# Drimp_Quadcopter.net
KiCad netlist of a schematic drawn in Altium Designer
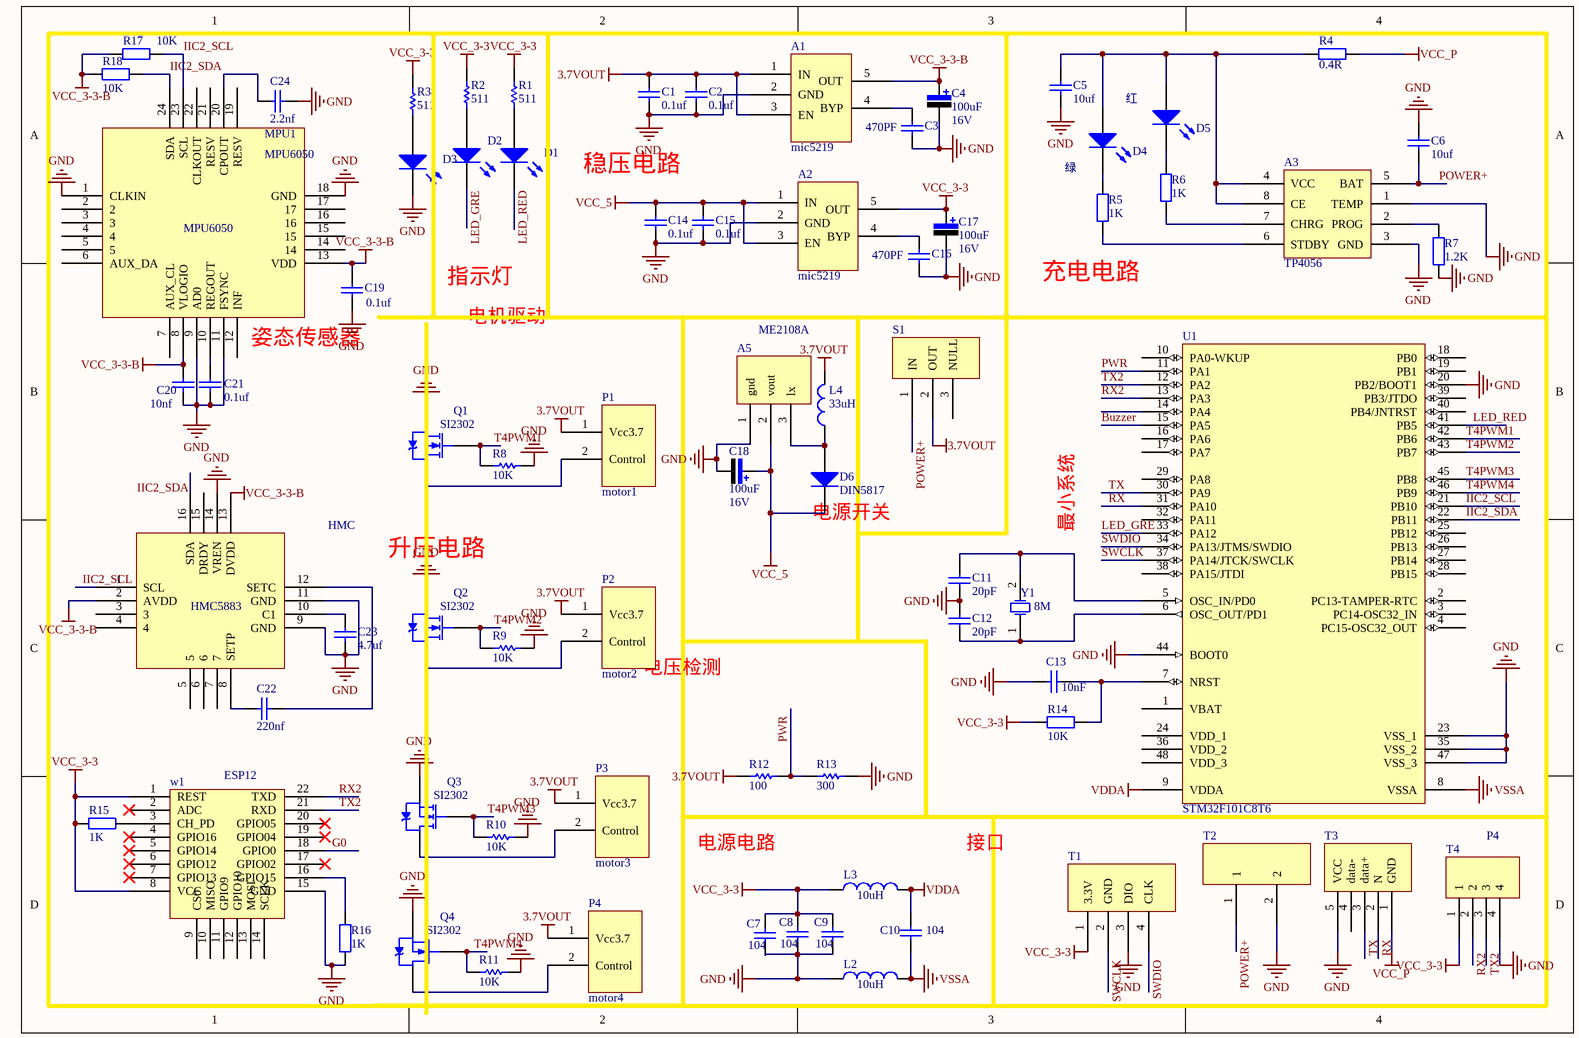
[diagram p0: Drimp_Quadcopter.SchDoc]

(export (version "E")
  (design (tool "Eeschema 10.0.6"))
  (components
    (comp (ref "A1")
      (value "mic5219")
      (footprint "SOT23-5")
      (description "低压差转3.3V")
      (libsource (lib "My") (part "mic5219"))
    )
    (comp (ref "A2")
      (value "mic5219")
      (footprint "SOT23-5")
      (description "低压差转3.3V")
      (libsource (lib "My") (part "mic5219"))
    )
    (comp (ref "A3") (value "TP4056") (footprint "SOP8") (libsource (lib "My") (part "TP4056")))
    (comp (ref "A5") (value "ME2108A") (footprint "SOT-89_M") (libsource (lib "My") (part "bl8530")))
    (comp (ref "C1")
      (value "0.1uf")
      (footprint "C-RAD-0603")
      (description "无极性电容")
      (fields (field (name "Comment") "Cap") (field (name "PUBLISHER") "Altium Limited"))
      (libsource (lib "Fszhang") (part "Cap"))
    )
    (comp (ref "C2")
      (value "0.1uf")
      (footprint "C-RAD-0603")
      (description "无极性电容")
      (fields (field (name "Comment") "Cap") (field (name "PUBLISHER") "Altium Limited"))
      (libsource (lib "Fszhang") (part "Cap"))
    )
    (comp (ref "C3")
      (value "470PF")
      (footprint "C-RAD-0603")
      (description "无极性电容")
      (fields (field (name "Comment") "Cap") (field (name "PUBLISHER") "Altium Limited"))
      (libsource (lib "Fszhang") (part "Cap"))
    )
    (comp (ref "C4")
      (value "100uF")
      (footprint "CAP-6032")
      (description "极性电解电容")
      (fields
        (field (name "VOL") "16V")
        (field (name "Comment") "Cap Pol")
        (field (name "PUBLISHER") "Altium Limited")
      )
      (libsource (lib "Fszhang") (part "Cap Pol"))
    )
    (comp (ref "C5")
      (value "10uf")
      (footprint "C-RAD-0603")
      (description "无极性电容")
      (fields (field (name "Comment") "Cap") (field (name "PUBLISHER") "Altium Limited"))
      (libsource (lib "Fszhang") (part "Cap"))
    )
    (comp (ref "C6")
      (value "10uf")
      (footprint "C-RAD-0603")
      (description "无极性电容")
      (fields (field (name "Comment") "Cap") (field (name "PUBLISHER") "Altium Limited"))
      (libsource (lib "Fszhang") (part "Cap"))
    )
    (comp (ref "C7")
      (value "104")
      (footprint "0603-N-CAP")
      (description "Capacitor")
      (fields (field (name "Comment") "Cap") (field (name "PUBLISHER") "Altium Limited"))
      (libsource (lib "Miscellaneous Devices") (part "Cap"))
    )
    (comp (ref "C8")
      (value "104")
      (footprint "0603-N-CAP")
      (description "Capacitor")
      (fields (field (name "Comment") "Cap") (field (name "PUBLISHER") "Altium Limited"))
      (libsource (lib "Miscellaneous Devices") (part "Cap"))
    )
    (comp (ref "C9")
      (value "104")
      (footprint "0603-N-CAP")
      (description "Capacitor")
      (fields (field (name "Comment") "Cap") (field (name "PUBLISHER") "Altium Limited"))
      (libsource (lib "Miscellaneous Devices") (part "Cap"))
    )
    (comp (ref "C10")
      (value "104")
      (footprint "0603-N-CAP")
      (description "Capacitor")
      (fields (field (name "Comment") "Cap") (field (name "PUBLISHER") "Altium Limited"))
      (libsource (lib "Miscellaneous Devices") (part "Cap"))
    )
    (comp (ref "C11")
      (value "20pF")
      (footprint "0603-N-CAP")
      (description "Capacitor")
      (fields (field (name "Comment") "Cap") (field (name "PUBLISHER") "Altium Limited"))
      (libsource (lib "Miscellaneous Devices") (part "Cap"))
    )
    (comp (ref "C12")
      (value "20pF")
      (footprint "0603-N-CAP")
      (description "Capacitor")
      (fields (field (name "Comment") "Cap") (field (name "PUBLISHER") "Altium Limited"))
      (libsource (lib "Miscellaneous Devices") (part "Cap"))
    )
    (comp (ref "C13")
      (value "10nF")
      (footprint "0603-N-CAP")
      (description "Capacitor")
      (fields (field (name "Comment") "Cap") (field (name "PUBLISHER") "Altium Limited"))
      (libsource (lib "Miscellaneous Devices") (part "Cap"))
    )
    (comp (ref "C14")
      (value "0.1uf")
      (footprint "C-RAD-0603")
      (description "无极性电容")
      (fields (field (name "Comment") "Cap") (field (name "PUBLISHER") "Altium Limited"))
      (libsource (lib "Fszhang") (part "Cap"))
    )
    (comp (ref "C15")
      (value "0.1uf")
      (footprint "C-RAD-0603")
      (description "无极性电容")
      (fields (field (name "Comment") "Cap") (field (name "PUBLISHER") "Altium Limited"))
      (libsource (lib "Fszhang") (part "Cap"))
    )
    (comp (ref "C16")
      (value "470PF")
      (footprint "C-RAD-0603")
      (description "无极性电容")
      (fields (field (name "Comment") "Cap") (field (name "PUBLISHER") "Altium Limited"))
      (libsource (lib "Fszhang") (part "Cap"))
    )
    (comp (ref "C17")
      (value "100uF")
      (footprint "CAP-6032")
      (description "极性电解电容")
      (fields
        (field (name "VOL") "16V")
        (field (name "Comment") "Cap Pol")
        (field (name "PUBLISHER") "Altium Limited")
      )
      (libsource (lib "Fszhang") (part "Cap Pol"))
    )
    (comp (ref "C18")
      (value "100uF")
      (footprint "CAP-6032")
      (description "极性电解电容")
      (fields
        (field (name "VOL") "16V")
        (field (name "Comment") "Cap Pol")
        (field (name "PUBLISHER") "Altium Limited")
      )
      (libsource (lib "") (part "Cap Pol_1"))
    )
    (comp (ref "C19")
      (value "0.1uf")
      (footprint "C-RAD-0603")
      (description "无极性电容")
      (fields (field (name "Comment") "Cap") (field (name "PUBLISHER") "Altium Limited"))
      (libsource (lib "Fszhang") (part "Cap"))
    )
    (comp (ref "C20")
      (value "10nf")
      (footprint "C-RAD-0603")
      (description "无极性电容")
      (fields (field (name "Comment") "Cap") (field (name "PUBLISHER") "Altium Limited"))
      (libsource (lib "Fszhang") (part "Cap"))
    )
    (comp (ref "C21")
      (value "0.1uf")
      (footprint "C-RAD-0603")
      (description "无极性电容")
      (fields (field (name "Comment") "Cap") (field (name "PUBLISHER") "Altium Limited"))
      (libsource (lib "Fszhang") (part "Cap"))
    )
    (comp (ref "C22")
      (value "220nf")
      (footprint "C-RAD-0603")
      (description "无极性电容")
      (fields (field (name "Comment") "Cap") (field (name "PUBLISHER") "Altium Limited"))
      (libsource (lib "Fszhang") (part "Cap"))
    )
    (comp (ref "C23")
      (value "4.7uf")
      (footprint "C-RAD-0603")
      (description "无极性电容")
      (fields (field (name "Comment") "Cap") (field (name "PUBLISHER") "Altium Limited"))
      (libsource (lib "Fszhang") (part "Cap"))
    )
    (comp (ref "C24")
      (value "2.2nf")
      (footprint "C-RAD-0603")
      (description "无极性电容")
      (fields (field (name "Comment") "Cap") (field (name "PUBLISHER") "Altium Limited"))
      (libsource (lib "Fszhang") (part "Cap"))
    )
    (comp (ref "D1")
      (value "D2")
      (footprint "6-0805_N")
      (description "Typical BLUE SiC LED")
      (fields (field (name "PUBLISHER") "Altium Limited"))
      (libsource (lib "Miscellaneous Devices") (part "LED3"))
    )
    (comp (ref "D2")
      (value "D2")
      (footprint "6-0805_N")
      (description "Typical BLUE SiC LED")
      (fields (field (name "PUBLISHER") "Altium Limited"))
      (libsource (lib "Miscellaneous Devices") (part "LED3"))
    )
    (comp (ref "D3")
      (value "D2")
      (footprint "6-0805_N")
      (description "Typical BLUE SiC LED")
      (fields (field (name "PUBLISHER") "Altium Limited"))
      (libsource (lib "Miscellaneous Devices") (part "LED3"))
    )
    (comp (ref "D4")
      (value "LED0")
      (footprint "LED0805G")
      (description "发光二极管")
      (fields (field (name "PUBLISHER") "Altium Limited"))
      (libsource (lib "Fszhang") (part "LED0"))
    )
    (comp (ref "D5")
      (value "LED0")
      (footprint "LED0805R")
      (description "发光二极管")
      (fields (field (name "PUBLISHER") "Altium Limited"))
      (libsource (lib "Fszhang") (part "LED0"))
    )
    (comp (ref "D6")
      (value "Diode")
      (footprint "DIODE-SMA")
      (description "二极管")
      (fields (field (name "TYPE") "DIN5817") (field (name "PUBLISHER") "Altium Limited"))
      (libsource (lib "Fszhang") (part "Diode"))
    )
    (comp (ref "HMC")
      (value "Component_1")
      (footprint "HMC5883")
      (libsource (lib "HMC5883") (part "Component_1"))
    )
    (comp (ref "L2")
      (value "10uH")
      (footprint "0603-N - res")
      (description "Inductor")
      (fields (field (name "PUBLISHER") "Altium Limited"))
      (libsource (lib "Miscellaneous Devices") (part "Inductor"))
    )
    (comp (ref "L3")
      (value "10uH")
      (footprint "0603-N - res")
      (description "Inductor")
      (fields (field (name "PUBLISHER") "Altium Limited"))
      (libsource (lib "Miscellaneous Devices") (part "Inductor"))
    )
    (comp (ref "L4")
      (value "33uH")
      (footprint "CD54NP")
      (description "电感")
      (fields (field (name "Comment") "Inductor") (field (name "PUBLISHER") "Altium Limited"))
      (libsource (lib "Fszhang") (part "Inductor"))
    )
    (comp (ref "MPU1") (value "MPU6050") (footprint "MPU6050") (libsource (lib "MPU6050") (part "MPU6050")))
    (comp (ref "P1")
      (value "motor1")
      (footprint "P2-T-1.25")
      (description "电机连接口")
      (libsource (lib "Schlib1") (part "motor"))
    )
    (comp (ref "P2")
      (value "motor2")
      (footprint "P2-T-1.25")
      (description "电机连接口")
      (libsource (lib "Schlib1") (part "motor"))
    )
    (comp (ref "P3")
      (value "motor3")
      (footprint "P2-T-1.25")
      (description "电机连接口")
      (libsource (lib "Schlib1") (part "motor"))
    )
    (comp (ref "P4")
      (value "motor4")
      (footprint "P2-T-1.25")
      (description "电机连接口")
      (libsource (lib "Schlib1") (part "motor"))
    )
    (comp (ref "Q1")
      (value "SI2302")
      (footprint "SOT-23_M")
      (description "HEXFET Power MOSFET")
      (fields (field (name "PUBLISHER") "Altium Limited"))
      (libsource (lib "IR Discrete MOSFET - Power") (part "IRLML2402"))
    )
    (comp (ref "Q2")
      (value "SI2302")
      (footprint "SOT-23_M")
      (description "HEXFET Power MOSFET")
      (fields (field (name "PUBLISHER") "Altium Limited"))
      (libsource (lib "IR Discrete MOSFET - Power") (part "IRLML2402"))
    )
    (comp (ref "Q3")
      (value "SI2302")
      (footprint "SOT-23_M")
      (description "HEXFET Power MOSFET")
      (fields (field (name "PUBLISHER") "Altium Limited"))
      (libsource (lib "IR Discrete MOSFET - Power") (part "IRLML2402"))
    )
    (comp (ref "Q4")
      (value "SI2302")
      (footprint "SOT-23_M")
      (description "HEXFET Power MOSFET")
      (fields (field (name "PUBLISHER") "Altium Limited"))
      (libsource (lib "IR Discrete MOSFET - Power") (part "IRLML2402"))
    )
    (comp (ref "R1")
      (value "511")
      (footprint "0603-N - res")
      (description "Resistor")
      (fields (field (name "Comment") "Res1") (field (name "PUBLISHER") "Altium Limited"))
      (libsource (lib "Miscellaneous Devices") (part "Res1"))
    )
    (comp (ref "R2")
      (value "511")
      (footprint "0603-N - res")
      (description "Resistor")
      (fields (field (name "Comment") "Res1") (field (name "PUBLISHER") "Altium Limited"))
      (libsource (lib "Miscellaneous Devices") (part "Res1"))
    )
    (comp (ref "R3")
      (value "511")
      (footprint "0603-N - res")
      (description "Resistor")
      (fields (field (name "Comment") "Res1") (field (name "PUBLISHER") "Altium Limited"))
      (libsource (lib "Miscellaneous Devices") (part "Res1"))
    )
    (comp (ref "R4")
      (value "0.4R")
      (footprint "1206")
      (description "贴片电阻")
      (fields (field (name "Comment") "Res1") (field (name "PUBLISHER") "Altium Limited"))
      (libsource (lib "") (part "Res1_1"))
    )
    (comp (ref "R5")
      (value "1K")
      (footprint "0603-1")
      (description "贴片电阻")
      (fields (field (name "Comment") "Res1") (field (name "PUBLISHER") "Altium Limited"))
      (libsource (lib "Fszhang") (part "Res1"))
    )
    (comp (ref "R6")
      (value "1K")
      (footprint "0603-1")
      (description "贴片电阻")
      (fields (field (name "Comment") "Res1") (field (name "PUBLISHER") "Altium Limited"))
      (libsource (lib "Fszhang") (part "Res1"))
    )
    (comp (ref "R7")
      (value "1.2K")
      (footprint "0603-1")
      (description "贴片电阻")
      (fields (field (name "Comment") "Res1") (field (name "PUBLISHER") "Altium Limited"))
      (libsource (lib "Fszhang") (part "Res1"))
    )
    (comp (ref "R8")
      (value "10K")
      (footprint "0603-N - res")
      (description "Resistor")
      (fields (field (name "Comment") "Res1") (field (name "PUBLISHER") "Altium Limited"))
      (libsource (lib "Miscellaneous Devices") (part "Res1"))
    )
    (comp (ref "R9")
      (value "10K")
      (footprint "0603-N - res")
      (description "Resistor")
      (fields (field (name "Comment") "Res1") (field (name "PUBLISHER") "Altium Limited"))
      (libsource (lib "Miscellaneous Devices") (part "Res1"))
    )
    (comp (ref "R10")
      (value "10K")
      (footprint "0603-N - res")
      (description "Resistor")
      (fields (field (name "Comment") "Res1") (field (name "PUBLISHER") "Altium Limited"))
      (libsource (lib "Miscellaneous Devices") (part "Res1"))
    )
    (comp (ref "R11")
      (value "10K")
      (footprint "0603-N - res")
      (description "Resistor")
      (fields (field (name "Comment") "Res1") (field (name "PUBLISHER") "Altium Limited"))
      (libsource (lib "Miscellaneous Devices") (part "Res1"))
    )
    (comp (ref "R12")
      (value "100")
      (footprint "0603-N - res")
      (description "Resistor")
      (fields (field (name "Comment") "Res1") (field (name "PUBLISHER") "Altium Limited"))
      (libsource (lib "Miscellaneous Devices") (part "Res1"))
    )
    (comp (ref "R13")
      (value "300")
      (footprint "0603-N - res")
      (description "Resistor")
      (fields (field (name "Comment") "Res1") (field (name "PUBLISHER") "Altium Limited"))
      (libsource (lib "Miscellaneous Devices") (part "Res1"))
    )
    (comp (ref "R14")
      (value "10K")
      (footprint "0603-N - res")
      (description "Resistor")
      (fields (field (name "Comment") "Res2") (field (name "PUBLISHER") "Altium Limited"))
      (libsource (lib "Miscellaneous Devices") (part "Res2"))
    )
    (comp (ref "R15")
      (value "1K")
      (footprint "0603-N - res")
      (description "Resistor")
      (fields (field (name "Comment") "Res2") (field (name "PUBLISHER") "Altium Limited"))
      (libsource (lib "Miscellaneous Devices") (part "Res2"))
    )
    (comp (ref "R16")
      (value "1K")
      (footprint "0603-N - res")
      (description "Resistor")
      (fields (field (name "Comment") "Res2") (field (name "PUBLISHER") "Altium Limited"))
      (libsource (lib "") (part "Res2_1"))
    )
    (comp (ref "R17")
      (value "10K")
      (footprint "0603-N - res")
      (description "Resistor")
      (fields (field (name "Comment") "Res2") (field (name "PUBLISHER") "Altium Limited"))
      (libsource (lib "Miscellaneous Devices") (part "Res2"))
    )
    (comp (ref "R18")
      (value "10K")
      (footprint "0603-N - res")
      (description "Resistor")
      (fields (field (name "Comment") "Res2") (field (name "PUBLISHER") "Altium Limited"))
      (libsource (lib "Miscellaneous Devices") (part "Res2"))
    )
    (comp (ref "S1") (value "switch") (footprint "拨动开关") (libsource (lib "Schlib1") (part "switch")))
    (comp (ref "T1")
      (value "SW_download")
      (footprint "P4_1.25")
      (libsource (lib "Schlib1") (part "SW_download"))
    )
    (comp (ref "T2") (value "P2") (footprint "P2") (libsource (lib "My") (part "P2")))
    (comp (ref "T3") (value "mini usb") (footprint "USB_MICRO_5S_B") (libsource (lib "My") (part "mini usb")))
    (comp (ref "T4") (value "P4") (footprint "P4_1.25") (libsource (lib "My") (part "P4")))
    (comp (ref "U1")
      (value "STM32F101C8T6")
      (footprint "LQFP48_N")
      (description "STM32 ARM-based 32-bit MCU with 64 Kbytes Flash, 48-pin LQFP, Industrial Temperature")
      (fields (field (name "PUBLISHER") "Altium Limited"))
      (libsource (lib "ST Microcontroller 32-Bit STM32") (part "STM32F101C8T6"))
    )
    (comp (ref "w1") (value "ESP12") (footprint "ESP_12_F") (libsource (lib "My") (part "ESP12")))
    (comp (ref "Y1")
      (value "8M")
      (footprint "5032_")
      (description "Crystal Oscillator")
      (fields (field (name "PUBLISHER") "Altium Limited"))
      (libsource (lib "Miscellaneous Devices") (part "XTAL"))
    )
  )
  (nets
    (net (code "1") (name "/Buzzer") (class "Default")
      (node (ref "U1") (pin "15") (pinfunction "PA5_15") (pintype "bidirectional"))
    )
    (net (code "2") (name "/G0") (class "Default")
      (node (ref "w1") (pin "18") (pinfunction "GPIO0_18") (pintype "passive"))
    )
    (net (code "3") (name "/IIC2_SCL") (class "Default")
      (node (ref "HMC") (pin "1") (pinfunction "SCL_1") (pintype "passive"))
      (node (ref "MPU1") (pin "23") (pinfunction "SCL_23") (pintype "passive"))
      (node (ref "R17") (pin "2") (pinfunction "2_2") (pintype "passive"))
      (node (ref "U1") (pin "21") (pinfunction "PB10_21") (pintype "bidirectional"))
    )
    (net (code "4") (name "/IIC2_SDA") (class "Default")
      (node (ref "HMC") (pin "16") (pinfunction "SDA_16") (pintype "passive"))
      (node (ref "MPU1") (pin "24") (pinfunction "SDA_24") (pintype "passive"))
      (node (ref "R18") (pin "2") (pinfunction "2_2") (pintype "passive"))
      (node (ref "U1") (pin "22") (pinfunction "PB11_22") (pintype "bidirectional"))
    )
    (net (code "5") (name "/LED_GRE") (class "Default")
      (node (ref "D2") (pin "2") (pinfunction "K_2") (pintype "passive"))
      (node (ref "U1") (pin "33") (pinfunction "PA12_33") (pintype "bidirectional"))
    )
    (net (code "6") (name "/LED_RED") (class "Default")
      (node (ref "D1") (pin "2") (pinfunction "K_2") (pintype "passive"))
      (node (ref "U1") (pin "41") (pinfunction "PB5_41") (pintype "bidirectional"))
    )
    (net (code "7") (name "/POWER+") (class "Default")
      (node (ref "A3") (pin "5") (pinfunction "BAT_5") (pintype "passive"))
      (node (ref "C6") (pin "1") (pinfunction "1_1") (pintype "passive"))
      (node (ref "S1") (pin "1") (pinfunction "IN_1") (pintype "passive"))
      (node (ref "T2") (pin "1") (pinfunction "1_1") (pintype "passive"))
    )
    (net (code "8") (name "/PWR") (class "Default")
      (node (ref "R12") (pin "2") (pinfunction "2_2") (pintype "passive"))
      (node (ref "R13") (pin "1") (pinfunction "1_1") (pintype "passive"))
      (node (ref "U1") (pin "11") (pinfunction "PA1_11") (pintype "bidirectional"))
    )
    (net (code "9") (name "/RX") (class "Default")
      (node (ref "T3") (pin "2") (pinfunction "N_2") (pintype "passive"))
      (node (ref "U1") (pin "31") (pinfunction "PA10_31") (pintype "bidirectional"))
    )
    (net (code "10") (name "/RX2") (class "Default")
      (node (ref "T4") (pin "2") (pinfunction "2_2") (pintype "passive"))
      (node (ref "U1") (pin "13") (pinfunction "PA3_13") (pintype "bidirectional"))
      (node (ref "w1") (pin "22") (pinfunction "TXD_22") (pintype "passive"))
    )
    (net (code "11") (name "/SWCLK") (class "Default")
      (node (ref "T1") (pin "2") (pinfunction "GND_2") (pintype "passive"))
      (node (ref "U1") (pin "37") (pinfunction "PA14/JTCK/SWCLK_37") (pintype "bidirectional"))
    )
    (net (code "12") (name "/SWDIO") (class "Default")
      (node (ref "T1") (pin "4") (pinfunction "CLK_4") (pintype "passive"))
      (node (ref "U1") (pin "34") (pinfunction "PA13/JTMS/SWDIO_34") (pintype "bidirectional"))
    )
    (net (code "13") (name "/T4PWM1") (class "Default")
      (node (ref "Q1") (pin "1") (pinfunction "G_1") (pintype "passive"))
      (node (ref "R8") (pin "1") (pinfunction "1_1") (pintype "passive"))
      (node (ref "U1") (pin "42") (pinfunction "PB6_42") (pintype "bidirectional"))
    )
    (net (code "14") (name "/T4PWM2") (class "Default")
      (node (ref "Q2") (pin "1") (pinfunction "G_1") (pintype "passive"))
      (node (ref "R9") (pin "1") (pinfunction "1_1") (pintype "passive"))
      (node (ref "U1") (pin "43") (pinfunction "PB7_43") (pintype "bidirectional"))
    )
    (net (code "15") (name "/T4PWM3") (class "Default")
      (node (ref "Q3") (pin "1") (pinfunction "G_1") (pintype "passive"))
      (node (ref "R10") (pin "1") (pinfunction "1_1") (pintype "passive"))
      (node (ref "U1") (pin "45") (pinfunction "PB8_45") (pintype "bidirectional"))
    )
    (net (code "16") (name "/T4PWM4") (class "Default")
      (node (ref "Q4") (pin "1") (pinfunction "G_1") (pintype "passive"))
      (node (ref "R11") (pin "1") (pinfunction "1_1") (pintype "passive"))
      (node (ref "U1") (pin "46") (pinfunction "PB9_46") (pintype "bidirectional"))
    )
    (net (code "17") (name "/TX") (class "Default")
      (node (ref "T3") (pin "3") (pinfunction "data+_3") (pintype "passive"))
      (node (ref "U1") (pin "30") (pinfunction "PA9_30") (pintype "bidirectional"))
    )
    (net (code "18") (name "/TX2") (class "Default")
      (node (ref "T4") (pin "3") (pinfunction "3_3") (pintype "passive"))
      (node (ref "U1") (pin "12") (pinfunction "PA2_12") (pintype "bidirectional"))
      (node (ref "w1") (pin "21") (pinfunction "RXD_21") (pintype "passive"))
    )
    (net (code "19") (name "3.7VOUT") (class "Default")
      (node (ref "A1") (pin "1") (pinfunction "IN_1") (pintype "passive"))
      (node (ref "A1") (pin "3") (pinfunction "EN_3") (pintype "passive"))
      (node (ref "C1") (pin "2") (pinfunction "2_2") (pintype "passive"))
      (node (ref "C2") (pin "2") (pinfunction "2_2") (pintype "passive"))
      (node (ref "L4") (pin "2") (pinfunction "2_2") (pintype "passive"))
      (node (ref "P1") (pin "1") (pinfunction "Vcc3.7_1") (pintype "passive"))
      (node (ref "P2") (pin "1") (pinfunction "Vcc3.7_1") (pintype "passive"))
      (node (ref "P3") (pin "1") (pinfunction "Vcc3.7_1") (pintype "passive"))
      (node (ref "P4") (pin "1") (pinfunction "Vcc3.7_1") (pintype "passive"))
      (node (ref "R12") (pin "1") (pinfunction "1_1") (pintype "passive"))
      (node (ref "S1") (pin "2") (pinfunction "OUT_2") (pintype "passive"))
    )
    (net (code "20") (name "GND") (class "Default")
      (node (ref "A1") (pin "2") (pinfunction "GND_2") (pintype "passive"))
      (node (ref "A2") (pin "2") (pinfunction "GND_2") (pintype "passive"))
      (node (ref "A3") (pin "1") (pinfunction "TEMP_1") (pintype "passive"))
      (node (ref "A3") (pin "3") (pinfunction "GND_3") (pintype "passive"))
      (node (ref "A5") (pin "1") (pinfunction "gnd_1") (pintype "passive"))
      (node (ref "C1") (pin "1") (pinfunction "1_1") (pintype "passive"))
      (node (ref "C11") (pin "1") (pinfunction "1_1") (pintype "passive"))
      (node (ref "C12") (pin "2") (pinfunction "2_2") (pintype "passive"))
      (node (ref "C13") (pin "1") (pinfunction "1_1") (pintype "passive"))
      (node (ref "C14") (pin "1") (pinfunction "1_1") (pintype "passive"))
      (node (ref "C15") (pin "1") (pinfunction "1_1") (pintype "passive"))
      (node (ref "C16") (pin "1") (pinfunction "1_1") (pintype "passive"))
      (node (ref "C17") (pin "2") (pinfunction "2_2") (pintype "passive"))
      (node (ref "C18") (pin "2") (pinfunction "2_2") (pintype "passive"))
      (node (ref "C19") (pin "1") (pinfunction "1_1") (pintype "passive"))
      (node (ref "C2") (pin "1") (pinfunction "1_1") (pintype "passive"))
      (node (ref "C20") (pin "1") (pinfunction "1_1") (pintype "passive"))
      (node (ref "C21") (pin "1") (pinfunction "1_1") (pintype "passive"))
      (node (ref "C23") (pin "1") (pinfunction "1_1") (pintype "passive"))
      (node (ref "C24") (pin "1") (pinfunction "1_1") (pintype "passive"))
      (node (ref "C3") (pin "1") (pinfunction "1_1") (pintype "passive"))
      (node (ref "C4") (pin "2") (pinfunction "2_2") (pintype "passive"))
      (node (ref "C5") (pin "1") (pinfunction "1_1") (pintype "passive"))
      (node (ref "C6") (pin "2") (pinfunction "2_2") (pintype "passive"))
      (node (ref "C7") (pin "1") (pinfunction "1_1") (pintype "passive"))
      (node (ref "C8") (pin "1") (pinfunction "1_1") (pintype "passive"))
      (node (ref "C9") (pin "1") (pinfunction "1_1") (pintype "passive"))
      (node (ref "D3") (pin "2") (pinfunction "K_2") (pintype "passive"))
      (node (ref "HMC") (pin "11") (pinfunction "GND_11") (pintype "passive"))
      (node (ref "HMC") (pin "14") (pinfunction "VREN_14") (pintype "passive"))
      (node (ref "HMC") (pin "9") (pinfunction "GND_9") (pintype "passive"))
      (node (ref "L2") (pin "1") (pinfunction "1_1") (pintype "passive"))
      (node (ref "MPU1") (pin "1") (pinfunction "CLKIN_1") (pintype "passive"))
      (node (ref "MPU1") (pin "11") (pinfunction "FSYNC_11") (pintype "passive"))
      (node (ref "MPU1") (pin "18") (pinfunction "GND_18") (pintype "passive"))
      (node (ref "MPU1") (pin "9") (pinfunction "AD0_9") (pintype "passive"))
      (node (ref "Q1") (pin "2") (pinfunction "S_2") (pintype "passive"))
      (node (ref "Q2") (pin "2") (pinfunction "S_2") (pintype "passive"))
      (node (ref "Q3") (pin "2") (pinfunction "S_2") (pintype "passive"))
      (node (ref "Q4") (pin "2") (pinfunction "S_2") (pintype "passive"))
      (node (ref "R10") (pin "2") (pinfunction "2_2") (pintype "passive"))
      (node (ref "R11") (pin "2") (pinfunction "2_2") (pintype "passive"))
      (node (ref "R13") (pin "2") (pinfunction "2_2") (pintype "passive"))
      (node (ref "R16") (pin "1") (pinfunction "1_1") (pintype "passive"))
      (node (ref "R7") (pin "2") (pinfunction "2_2") (pintype "passive"))
      (node (ref "R8") (pin "2") (pinfunction "2_2") (pintype "passive"))
      (node (ref "R9") (pin "2") (pinfunction "2_2") (pintype "passive"))
      (node (ref "T1") (pin "3") (pinfunction "DIO_3") (pintype "passive"))
      (node (ref "T2") (pin "2") (pinfunction "2_2") (pintype "passive"))
      (node (ref "T3") (pin "5") (pinfunction "VCC_5") (pintype "passive"))
      (node (ref "T4") (pin "4") (pinfunction "4_4") (pintype "passive"))
      (node (ref "U1") (pin "20") (pinfunction "PB2/BOOT1_20") (pintype "bidirectional"))
      (node (ref "U1") (pin "23") (pinfunction "VSS_1_23") (pintype "power_in"))
      (node (ref "U1") (pin "35") (pinfunction "VSS_2_35") (pintype "power_in"))
      (node (ref "U1") (pin "44") (pinfunction "BOOT0_44") (pintype "input"))
      (node (ref "U1") (pin "47") (pinfunction "VSS_3_47") (pintype "power_in"))
      (node (ref "w1") (pin "15") (pinfunction "GND_15") (pintype "passive"))
    )
    (net (code "21") (name "Net-(A1-BYP)") (class "Default")
      (node (ref "A1") (pin "4") (pinfunction "BYP_4") (pintype "passive"))
      (node (ref "C3") (pin "2") (pinfunction "2_2") (pintype "passive"))
    )
    (net (code "22") (name "Net-(A2-BYP)") (class "Default")
      (node (ref "A2") (pin "4") (pinfunction "BYP_4") (pintype "passive"))
      (node (ref "C16") (pin "2") (pinfunction "2_2") (pintype "passive"))
    )
    (net (code "23") (name "Net-(A3-CE)") (class "Default")
      (node (ref "A3") (pin "4") (pinfunction "VCC_4") (pintype "passive"))
      (node (ref "A3") (pin "8") (pinfunction "CE_8") (pintype "passive"))
      (node (ref "C5") (pin "2") (pinfunction "2_2") (pintype "passive"))
      (node (ref "D4") (pin "1") (pinfunction "A_1") (pintype "passive"))
      (node (ref "D5") (pin "1") (pinfunction "A_1") (pintype "passive"))
      (node (ref "R4") (pin "1") (pinfunction "1_1") (pintype "passive"))
    )
    (net (code "24") (name "Net-(A3-CHRG)") (class "Default")
      (node (ref "A3") (pin "7") (pinfunction "CHRG_7") (pintype "passive"))
      (node (ref "R6") (pin "2") (pinfunction "2_2") (pintype "passive"))
    )
    (net (code "25") (name "Net-(A3-PROG)") (class "Default")
      (node (ref "A3") (pin "2") (pinfunction "PROG_2") (pintype "passive"))
      (node (ref "R7") (pin "1") (pinfunction "1_1") (pintype "passive"))
    )
    (net (code "26") (name "Net-(A3-STDBY)") (class "Default")
      (node (ref "A3") (pin "6") (pinfunction "STDBY_6") (pintype "passive"))
      (node (ref "R5") (pin "2") (pinfunction "2_2") (pintype "passive"))
    )
    (net (code "27") (name "Net-(A5-lx)") (class "Default")
      (node (ref "A5") (pin "3") (pinfunction "lx_3") (pintype "passive"))
      (node (ref "D6") (pin "1") (pinfunction "A_1") (pintype "passive"))
      (node (ref "L4") (pin "1") (pinfunction "1_1") (pintype "passive"))
    )
    (net (code "28") (name "Net-(D1-A)") (class "Default")
      (node (ref "D1") (pin "1") (pinfunction "A_1") (pintype "passive"))
      (node (ref "R1") (pin "1") (pinfunction "1_1") (pintype "passive"))
    )
    (net (code "29") (name "Net-(D2-A)") (class "Default")
      (node (ref "D2") (pin "1") (pinfunction "A_1") (pintype "passive"))
      (node (ref "R2") (pin "1") (pinfunction "1_1") (pintype "passive"))
    )
    (net (code "30") (name "Net-(D3-A)") (class "Default")
      (node (ref "D3") (pin "1") (pinfunction "A_1") (pintype "passive"))
      (node (ref "R3") (pin "1") (pinfunction "1_1") (pintype "passive"))
    )
    (net (code "31") (name "Net-(D4-K)") (class "Default")
      (node (ref "D4") (pin "2") (pinfunction "K_2") (pintype "passive"))
      (node (ref "R5") (pin "1") (pinfunction "1_1") (pintype "passive"))
    )
    (net (code "32") (name "Net-(D5-K)") (class "Default")
      (node (ref "D5") (pin "2") (pinfunction "K_2") (pintype "passive"))
      (node (ref "R6") (pin "1") (pinfunction "1_1") (pintype "passive"))
    )
    (net (code "33") (name "Net-(HMC-C1)") (class "Default")
      (node (ref "C23") (pin "2") (pinfunction "2_2") (pintype "passive"))
      (node (ref "HMC") (pin "10") (pinfunction "C1_10") (pintype "passive"))
    )
    (net (code "34") (name "Net-(HMC-SETC)") (class "Default")
      (node (ref "C22") (pin "1") (pinfunction "1_1") (pintype "passive"))
      (node (ref "HMC") (pin "12") (pinfunction "SETC_12") (pintype "passive"))
    )
    (net (code "35") (name "Net-(HMC-SETP)") (class "Default")
      (node (ref "C22") (pin "2") (pinfunction "2_2") (pintype "passive"))
      (node (ref "HMC") (pin "8") (pinfunction "SETP_8") (pintype "passive"))
    )
    (net (code "36") (name "Net-(MPU1-CPOUT)") (class "Default")
      (node (ref "C24") (pin "2") (pinfunction "2_2") (pintype "passive"))
      (node (ref "MPU1") (pin "20") (pinfunction "CPOUT_20") (pintype "passive"))
    )
    (net (code "37") (name "Net-(MPU1-REGOUT)") (class "Default")
      (node (ref "C21") (pin "2") (pinfunction "2_2") (pintype "passive"))
      (node (ref "MPU1") (pin "10") (pinfunction "REGOUT_10") (pintype "passive"))
    )
    (net (code "38") (name "Net-(P1-Control)") (class "Default")
      (node (ref "P1") (pin "2") (pinfunction "Control_2") (pintype "passive"))
      (node (ref "Q1") (pin "3") (pinfunction "D_3") (pintype "passive"))
    )
    (net (code "39") (name "Net-(P2-Control)") (class "Default")
      (node (ref "P2") (pin "2") (pinfunction "Control_2") (pintype "passive"))
      (node (ref "Q2") (pin "3") (pinfunction "D_3") (pintype "passive"))
    )
    (net (code "40") (name "Net-(P3-Control)") (class "Default")
      (node (ref "P3") (pin "2") (pinfunction "Control_2") (pintype "passive"))
      (node (ref "Q3") (pin "3") (pinfunction "D_3") (pintype "passive"))
    )
    (net (code "41") (name "Net-(P4-Control)") (class "Default")
      (node (ref "P4") (pin "2") (pinfunction "Control_2") (pintype "passive"))
      (node (ref "Q4") (pin "3") (pinfunction "D_3") (pintype "passive"))
    )
    (net (code "42") (name "Net-(U1-NRST)") (class "Default")
      (node (ref "C13") (pin "2") (pinfunction "2_2") (pintype "passive"))
      (node (ref "R14") (pin "2") (pinfunction "2_2") (pintype "passive"))
      (node (ref "U1") (pin "7") (pinfunction "NRST_7") (pintype "bidirectional"))
    )
    (net (code "43") (name "Net-(U1-OSC_IN{slash}PD0)") (class "Default")
      (node (ref "C11") (pin "2") (pinfunction "2_2") (pintype "passive"))
      (node (ref "U1") (pin "5") (pinfunction "OSC_IN/PD0_5") (pintype "input"))
      (node (ref "Y1") (pin "2") (pinfunction "OSC2_2") (pintype "passive"))
    )
    (net (code "44") (name "Net-(U1-OSC_OUT{slash}PD1)") (class "Default")
      (node (ref "C12") (pin "1") (pinfunction "1_1") (pintype "passive"))
      (node (ref "U1") (pin "6") (pinfunction "OSC_OUT/PD1_6") (pintype "output"))
      (node (ref "Y1") (pin "1") (pinfunction "OSC1_1") (pintype "passive"))
    )
    (net (code "45") (name "Net-(w1-CH_PD)") (class "Default")
      (node (ref "R15") (pin "2") (pinfunction "2_2") (pintype "passive"))
      (node (ref "w1") (pin "3") (pinfunction "CH_PD_3") (pintype "passive"))
    )
    (net (code "46") (name "Net-(w1-GPIO15)") (class "Default")
      (node (ref "R16") (pin "2") (pinfunction "2_2") (pintype "passive"))
      (node (ref "w1") (pin "16") (pinfunction "GPIO15_16") (pintype "passive"))
    )
    (net (code "47") (name "VCC_3-3") (class "Default")
      (node (ref "A2") (pin "5") (pinfunction "OUT_5") (pintype "passive"))
      (node (ref "C17") (pin "1") (pinfunction "1_1") (pintype "passive"))
      (node (ref "C7") (pin "2") (pinfunction "2_2") (pintype "passive"))
      (node (ref "C8") (pin "2") (pinfunction "2_2") (pintype "passive"))
      (node (ref "C9") (pin "2") (pinfunction "2_2") (pintype "passive"))
      (node (ref "L3") (pin "1") (pinfunction "1_1") (pintype "passive"))
      (node (ref "R1") (pin "2") (pinfunction "2_2") (pintype "passive"))
      (node (ref "R14") (pin "1") (pinfunction "1_1") (pintype "passive"))
      (node (ref "R15") (pin "1") (pinfunction "1_1") (pintype "passive"))
      (node (ref "R2") (pin "2") (pinfunction "2_2") (pintype "passive"))
      (node (ref "R3") (pin "2") (pinfunction "2_2") (pintype "passive"))
      (node (ref "T1") (pin "1") (pinfunction "3.3V_1") (pintype "passive"))
      (node (ref "T4") (pin "1") (pinfunction "1_1") (pintype "passive"))
      (node (ref "w1") (pin "1") (pinfunction "REST_1") (pintype "passive"))
      (node (ref "w1") (pin "8") (pinfunction "VCC_8") (pintype "passive"))
    )
    (net (code "48") (name "VCC_3-3-B") (class "Default")
      (node (ref "A1") (pin "5") (pinfunction "OUT_5") (pintype "passive"))
      (node (ref "C19") (pin "2") (pinfunction "2_2") (pintype "passive"))
      (node (ref "C20") (pin "2") (pinfunction "2_2") (pintype "passive"))
      (node (ref "C4") (pin "1") (pinfunction "1_1") (pintype "passive"))
      (node (ref "HMC") (pin "13") (pinfunction "DVDD_13") (pintype "passive"))
      (node (ref "HMC") (pin "2") (pinfunction "AVDD_2") (pintype "passive"))
      (node (ref "MPU1") (pin "13") (pinfunction "VDD_13") (pintype "passive"))
      (node (ref "MPU1") (pin "8") (pinfunction "VLOGIO_8") (pintype "passive"))
      (node (ref "R17") (pin "1") (pinfunction "1_1") (pintype "passive"))
      (node (ref "R18") (pin "1") (pinfunction "1_1") (pintype "passive"))
    )
    (net (code "49") (name "VCC_5") (class "Default")
      (node (ref "A2") (pin "1") (pinfunction "IN_1") (pintype "passive"))
      (node (ref "A2") (pin "3") (pinfunction "EN_3") (pintype "passive"))
      (node (ref "A5") (pin "2") (pinfunction "vout_2") (pintype "passive"))
      (node (ref "C14") (pin "2") (pinfunction "2_2") (pintype "passive"))
      (node (ref "C15") (pin "2") (pinfunction "2_2") (pintype "passive"))
      (node (ref "C18") (pin "1") (pinfunction "1_1") (pintype "passive"))
      (node (ref "D6") (pin "2") (pinfunction "K_2") (pintype "passive"))
    )
    (net (code "50") (name "VCC_P") (class "Default")
      (node (ref "R4") (pin "2") (pinfunction "2_2") (pintype "passive"))
      (node (ref "T3") (pin "1") (pinfunction "GND_1") (pintype "passive"))
    )
    (net (code "51") (name "VDDA") (class "Default")
      (node (ref "C10") (pin "2") (pinfunction "2_2") (pintype "passive"))
      (node (ref "L3") (pin "2") (pinfunction "2_2") (pintype "passive"))
      (node (ref "U1") (pin "9") (pinfunction "VDDA_9") (pintype "power_in"))
    )
    (net (code "52") (name "VSSA") (class "Default")
      (node (ref "C10") (pin "1") (pinfunction "1_1") (pintype "passive"))
      (node (ref "L2") (pin "2") (pinfunction "2_2") (pintype "passive"))
      (node (ref "U1") (pin "8") (pinfunction "VSSA_8") (pintype "power_in"))
    )
    (net (code "53") (name "unconnected-(HMC-DRDY-Pad15)") (class "Default")
      (node (ref "HMC") (pin "15") (pinfunction "DRDY_15") (pintype "passive"))
    )
    (net (code "54") (name "unconnected-(HMC-Pad3)") (class "Default")
      (node (ref "HMC") (pin "3") (pinfunction "3_3") (pintype "passive"))
    )
    (net (code "55") (name "unconnected-(HMC-Pad4)") (class "Default")
      (node (ref "HMC") (pin "4") (pinfunction "4_4") (pintype "passive"))
    )
    (net (code "56") (name "unconnected-(HMC-Pad5)") (class "Default")
      (node (ref "HMC") (pin "5") (pinfunction "5_5") (pintype "passive"))
    )
    (net (code "57") (name "unconnected-(HMC-Pad6)") (class "Default")
      (node (ref "HMC") (pin "6") (pinfunction "6_6") (pintype "passive"))
    )
    (net (code "58") (name "unconnected-(HMC-Pad7)") (class "Default")
      (node (ref "HMC") (pin "7") (pinfunction "7_7") (pintype "passive"))
    )
    (net (code "59") (name "unconnected-(MPU1-AUX_CL-Pad7)") (class "Default")
      (node (ref "MPU1") (pin "7") (pinfunction "AUX_CL_7") (pintype "passive"))
    )
    (net (code "60") (name "unconnected-(MPU1-AUX_DA-Pad6)") (class "Default")
      (node (ref "MPU1") (pin "6") (pinfunction "AUX_DA_6") (pintype "passive"))
    )
    (net (code "61") (name "unconnected-(MPU1-CLKOUT-Pad22)") (class "Default")
      (node (ref "MPU1") (pin "22") (pinfunction "CLKOUT_22") (pintype "passive"))
    )
    (net (code "62") (name "unconnected-(MPU1-INF-Pad12)") (class "Default")
      (node (ref "MPU1") (pin "12") (pinfunction "INF_12") (pintype "passive"))
    )
    (net (code "63") (name "unconnected-(MPU1-Pad2)") (class "Default")
      (node (ref "MPU1") (pin "2") (pinfunction "2_2") (pintype "passive"))
    )
    (net (code "64") (name "unconnected-(MPU1-Pad3)") (class "Default")
      (node (ref "MPU1") (pin "3") (pinfunction "3_3") (pintype "passive"))
    )
    (net (code "65") (name "unconnected-(MPU1-Pad4)") (class "Default")
      (node (ref "MPU1") (pin "4") (pinfunction "4_4") (pintype "passive"))
    )
    (net (code "66") (name "unconnected-(MPU1-Pad5)") (class "Default")
      (node (ref "MPU1") (pin "5") (pinfunction "5_5") (pintype "passive"))
    )
    (net (code "67") (name "unconnected-(MPU1-Pad14)") (class "Default")
      (node (ref "MPU1") (pin "14") (pinfunction "14_14") (pintype "passive"))
    )
    (net (code "68") (name "unconnected-(MPU1-Pad15)") (class "Default")
      (node (ref "MPU1") (pin "15") (pinfunction "15_15") (pintype "passive"))
    )
    (net (code "69") (name "unconnected-(MPU1-Pad16)") (class "Default")
      (node (ref "MPU1") (pin "16") (pinfunction "16_16") (pintype "passive"))
    )
    (net (code "70") (name "unconnected-(MPU1-Pad17)") (class "Default")
      (node (ref "MPU1") (pin "17") (pinfunction "17_17") (pintype "passive"))
    )
    (net (code "71") (name "unconnected-(MPU1-RESV-Pad19)") (class "Default")
      (node (ref "MPU1") (pin "19") (pinfunction "RESV_19") (pintype "passive"))
    )
    (net (code "72") (name "unconnected-(MPU1-RESV-Pad21)") (class "Default")
      (node (ref "MPU1") (pin "21") (pinfunction "RESV_21") (pintype "passive"))
    )
    (net (code "73") (name "unconnected-(S1-NULL-Pad3)") (class "Default")
      (node (ref "S1") (pin "3") (pinfunction "NULL_3") (pintype "passive"))
    )
    (net (code "74") (name "unconnected-(T3-data--Pad4)") (class "Default")
      (node (ref "T3") (pin "4") (pinfunction "data-_4") (pintype "passive"))
    )
    (net (code "75") (name "unconnected-(U1-PA0-WKUP-Pad10)") (class "Default")
      (node (ref "U1") (pin "10") (pinfunction "PA0-WKUP_10") (pintype "bidirectional"))
    )
    (net (code "76") (name "unconnected-(U1-PA4-Pad14)") (class "Default")
      (node (ref "U1") (pin "14") (pinfunction "PA4_14") (pintype "bidirectional"))
    )
    (net (code "77") (name "unconnected-(U1-PA6-Pad16)") (class "Default")
      (node (ref "U1") (pin "16") (pinfunction "PA6_16") (pintype "bidirectional"))
    )
    (net (code "78") (name "unconnected-(U1-PA7-Pad17)") (class "Default")
      (node (ref "U1") (pin "17") (pinfunction "PA7_17") (pintype "bidirectional"))
    )
    (net (code "79") (name "unconnected-(U1-PA8-Pad29)") (class "Default")
      (node (ref "U1") (pin "29") (pinfunction "PA8_29") (pintype "bidirectional"))
    )
    (net (code "80") (name "unconnected-(U1-PA11-Pad32)") (class "Default")
      (node (ref "U1") (pin "32") (pinfunction "PA11_32") (pintype "bidirectional"))
    )
    (net (code "81") (name "unconnected-(U1-PA15{slash}JTDI-Pad38)") (class "Default")
      (node (ref "U1") (pin "38") (pinfunction "PA15/JTDI_38") (pintype "bidirectional"))
    )
    (net (code "82") (name "unconnected-(U1-PB0-Pad18)") (class "Default")
      (node (ref "U1") (pin "18") (pinfunction "PB0_18") (pintype "bidirectional"))
    )
    (net (code "83") (name "unconnected-(U1-PB1-Pad19)") (class "Default")
      (node (ref "U1") (pin "19") (pinfunction "PB1_19") (pintype "bidirectional"))
    )
    (net (code "84") (name "unconnected-(U1-PB3{slash}JTDO-Pad39)") (class "Default")
      (node (ref "U1") (pin "39") (pinfunction "PB3/JTDO_39") (pintype "bidirectional"))
    )
    (net (code "85") (name "unconnected-(U1-PB4{slash}JNTRST-Pad40)") (class "Default")
      (node (ref "U1") (pin "40") (pinfunction "PB4/JNTRST_40") (pintype "bidirectional"))
    )
    (net (code "86") (name "unconnected-(U1-PB12-Pad25)") (class "Default")
      (node (ref "U1") (pin "25") (pinfunction "PB12_25") (pintype "bidirectional"))
    )
    (net (code "87") (name "unconnected-(U1-PB13-Pad26)") (class "Default")
      (node (ref "U1") (pin "26") (pinfunction "PB13_26") (pintype "bidirectional"))
    )
    (net (code "88") (name "unconnected-(U1-PB14-Pad27)") (class "Default")
      (node (ref "U1") (pin "27") (pinfunction "PB14_27") (pintype "bidirectional"))
    )
    (net (code "89") (name "unconnected-(U1-PB15-Pad28)") (class "Default")
      (node (ref "U1") (pin "28") (pinfunction "PB15_28") (pintype "bidirectional"))
    )
    (net (code "90") (name "unconnected-(U1-PC13-TAMPER-RTC-Pad2)") (class "Default")
      (node (ref "U1") (pin "2") (pinfunction "PC13-TAMPER-RTC_2") (pintype "bidirectional"))
    )
    (net (code "91") (name "unconnected-(U1-PC14-OSC32_IN-Pad3)") (class "Default")
      (node (ref "U1") (pin "3") (pinfunction "PC14-OSC32_IN_3") (pintype "bidirectional"))
    )
    (net (code "92") (name "unconnected-(U1-PC15-OSC32_OUT-Pad4)") (class "Default")
      (node (ref "U1") (pin "4") (pinfunction "PC15-OSC32_OUT_4") (pintype "bidirectional"))
    )
    (net (code "93") (name "unconnected-(U1-VBAT-Pad1)") (class "Default")
      (node (ref "U1") (pin "1") (pinfunction "VBAT_1") (pintype "power_in"))
    )
    (net (code "94") (name "unconnected-(U1-VDD_1-Pad24)") (class "Default")
      (node (ref "U1") (pin "24") (pinfunction "VDD_1_24") (pintype "power_in"))
    )
    (net (code "95") (name "unconnected-(U1-VDD_2-Pad36)") (class "Default")
      (node (ref "U1") (pin "36") (pinfunction "VDD_2_36") (pintype "power_in"))
    )
    (net (code "96") (name "unconnected-(U1-VDD_3-Pad48)") (class "Default")
      (node (ref "U1") (pin "48") (pinfunction "VDD_3_48") (pintype "power_in"))
    )
    (net (code "97") (name "unconnected-(w1-ADC-Pad2)") (class "Default")
      (node (ref "w1") (pin "2") (pinfunction "ADC_2") (pintype "passive+no_connect"))
    )
    (net (code "98") (name "unconnected-(w1-CS0-Pad9)") (class "Default")
      (node (ref "w1") (pin "9") (pinfunction "CS0_9") (pintype "passive"))
    )
    (net (code "99") (name "unconnected-(w1-GPIO02-Pad17)") (class "Default")
      (node (ref "w1") (pin "17") (pinfunction "GPIO02_17") (pintype "passive+no_connect"))
    )
    (net (code "100") (name "unconnected-(w1-GPIO04-Pad19)") (class "Default")
      (node (ref "w1") (pin "19") (pinfunction "GPIO04_19") (pintype "passive+no_connect"))
    )
    (net (code "101") (name "unconnected-(w1-GPIO05-Pad20)") (class "Default")
      (node (ref "w1") (pin "20") (pinfunction "GPIO05_20") (pintype "passive+no_connect"))
    )
    (net (code "102") (name "unconnected-(w1-GPIO9-Pad11)") (class "Default")
      (node (ref "w1") (pin "11") (pinfunction "GPIO9_11") (pintype "passive"))
    )
    (net (code "103") (name "unconnected-(w1-GPIO10-Pad12)") (class "Default")
      (node (ref "w1") (pin "12") (pinfunction "GPIO10_12") (pintype "passive"))
    )
    (net (code "104") (name "unconnected-(w1-GPIO12-Pad6)") (class "Default")
      (node (ref "w1") (pin "6") (pinfunction "GPIO12_6") (pintype "passive+no_connect"))
    )
    (net (code "105") (name "unconnected-(w1-GPIO13-Pad7)") (class "Default")
      (node (ref "w1") (pin "7") (pinfunction "GPIO13_7") (pintype "passive+no_connect"))
    )
    (net (code "106") (name "unconnected-(w1-GPIO14-Pad5)") (class "Default")
      (node (ref "w1") (pin "5") (pinfunction "GPIO14_5") (pintype "passive+no_connect"))
    )
    (net (code "107") (name "unconnected-(w1-GPIO16-Pad4)") (class "Default")
      (node (ref "w1") (pin "4") (pinfunction "GPIO16_4") (pintype "passive+no_connect"))
    )
    (net (code "108") (name "unconnected-(w1-MISO-Pad10)") (class "Default")
      (node (ref "w1") (pin "10") (pinfunction "MISO_10") (pintype "passive"))
    )
    (net (code "109") (name "unconnected-(w1-MOSI-Pad13)") (class "Default")
      (node (ref "w1") (pin "13") (pinfunction "MOSI_13") (pintype "passive"))
    )
    (net (code "110") (name "unconnected-(w1-SCLK-Pad14)") (class "Default")
      (node (ref "w1") (pin "14") (pinfunction "SCLK_14") (pintype "passive"))
    )
  )
)
